# RS485.net
KiCad netlist of a schematic drawn in Altium Designer
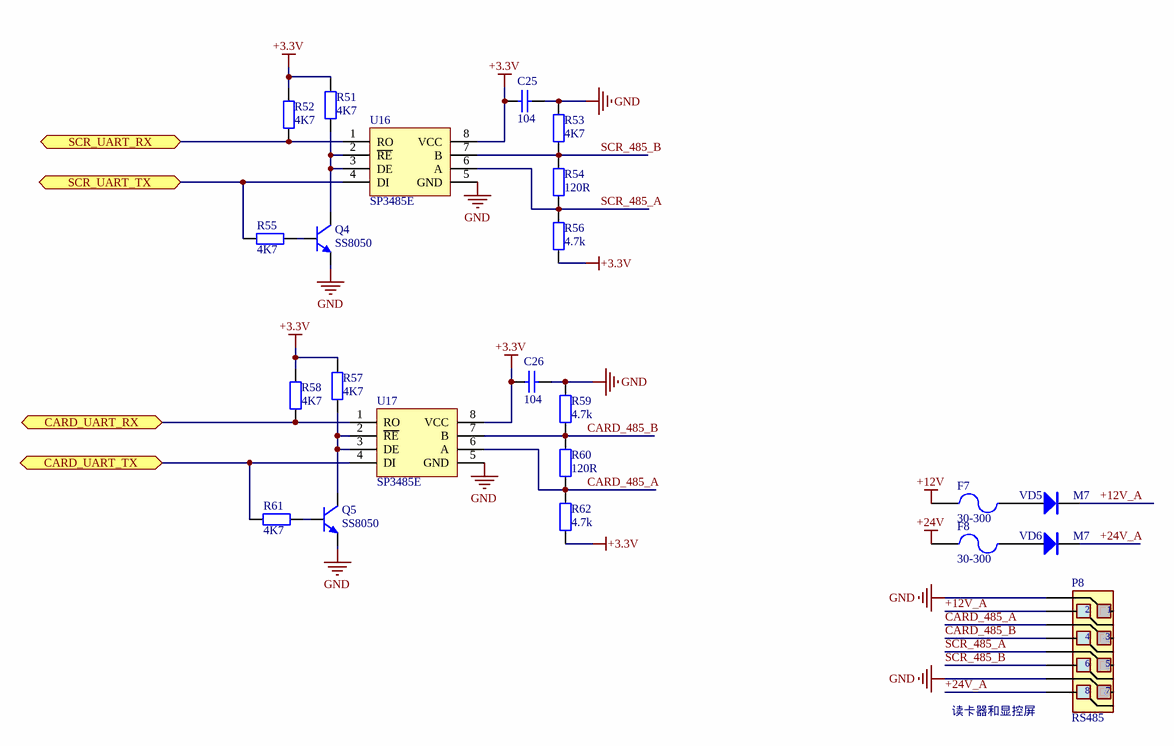
[diagram p0: RS485.SchDoc]

(export (version "E")
  (design (tool "Eeschema 10.0.6"))
  (components
    (comp (ref "C25")
      (value "104")
      (footprint "C 0805")
      (libsource (lib "YXF_ComponentLibrary") (part "Cap1"))
    )
    (comp (ref "C26")
      (value "104")
      (footprint "C 0805")
      (libsource (lib "YXF_ComponentLibrary") (part "Cap1"))
    )
    (comp (ref "F7")
      (value "30-300")
      (footprint "FU 1812")
      (description "Fuse")
      (fields (field (name "PUBLISHER") "Altium Limited"))
      (libsource (lib "YXF_ComponentLibrary") (part "Fuse 2"))
    )
    (comp (ref "F8")
      (value "30-300")
      (footprint "FU 1812")
      (description "Fuse")
      (fields (field (name "PUBLISHER") "Altium Limited"))
      (libsource (lib "YXF_ComponentLibrary") (part "Fuse 2"))
    )
    (comp (ref "P8")
      (value "RS485")
      (footprint "557-2x4")
      (description "接插件")
      (libsource (lib "YXF_ComponentLibrary") (part "557-2x4"))
    )
    (comp (ref "Q4")
      (value "SS8050")
      (footprint "SOT23-3N")
      (description "高频放大-NPN型")
      (fields (field (name "版权归属") "源创客"))
      (libsource (lib "三极管") (part "8050-SMD"))
    )
    (comp (ref "Q5")
      (value "SS8050")
      (footprint "SOT23-3N")
      (description "高频放大-NPN型")
      (fields (field (name "版权归属") "源创客"))
      (libsource (lib "三极管") (part "8050-SMD"))
    )
    (comp (ref "R51") (value "4K7") (footprint "R 0805") (libsource (lib "any") (part "Res1")))
    (comp (ref "R52") (value "4K7") (footprint "R 0805") (libsource (lib "any") (part "Res1")))
    (comp (ref "R53") (value "4K7") (footprint "R 0805") (libsource (lib "any") (part "Res1")))
    (comp (ref "R54") (value "120R") (footprint "R 0805") (libsource (lib "any") (part "Res1")))
    (comp (ref "R55") (value "4K7") (footprint "R 0805") (libsource (lib "") (part "Res1_1")))
    (comp (ref "R56") (value "4.7k") (footprint "R 0805") (libsource (lib "any") (part "Res1")))
    (comp (ref "R57") (value "4K7") (footprint "R 0805") (libsource (lib "any") (part "Res1")))
    (comp (ref "R58") (value "4K7") (footprint "R 0805") (libsource (lib "any") (part "Res1")))
    (comp (ref "R59") (value "4.7k") (footprint "R 0805") (libsource (lib "any") (part "Res1")))
    (comp (ref "R60") (value "120R") (footprint "R 0805") (libsource (lib "any") (part "Res1")))
    (comp (ref "R61") (value "4K7") (footprint "R 0805") (libsource (lib "") (part "Res1_1")))
    (comp (ref "R62") (value "4.7k") (footprint "R 0805") (libsource (lib "any") (part "Res1")))
    (comp (ref "U16") (value "SP3485E") (footprint "SOP8_N") (libsource (lib "YS_STM32f103") (part "SP3485")))
    (comp (ref "U17") (value "SP3485E") (footprint "SOP8_N") (libsource (lib "YS_STM32f103") (part "SP3485")))
    (comp (ref "VD5")
      (value "M7")
      (footprint "SMA")
      (description "整流二极管")
      (fields (field (name "版权归属") "源创客"))
      (libsource (lib "二极管-整流桥") (part "M7"))
    )
    (comp (ref "VD6")
      (value "M7")
      (footprint "SMA")
      (description "整流二极管")
      (fields (field (name "版权归属") "源创客"))
      (libsource (lib "二极管-整流桥") (part "M7"))
    )
  )
  (nets
    (net (code "1") (name "+3.3V") (class "Default")
      (node (ref "C25") (pin "2") (pinfunction "2_2") (pintype "passive"))
      (node (ref "C26") (pin "2") (pinfunction "2_2") (pintype "passive"))
      (node (ref "R51") (pin "2") (pinfunction "2_2") (pintype "passive"))
      (node (ref "R52") (pin "2") (pinfunction "2_2") (pintype "passive"))
      (node (ref "R56") (pin "1") (pinfunction "1_1") (pintype "passive"))
      (node (ref "R57") (pin "2") (pinfunction "2_2") (pintype "passive"))
      (node (ref "R58") (pin "2") (pinfunction "2_2") (pintype "passive"))
      (node (ref "R62") (pin "1") (pinfunction "1_1") (pintype "passive"))
      (node (ref "U16") (pin "8") (pinfunction "VCC_8") (pintype "passive"))
      (node (ref "U17") (pin "8") (pinfunction "VCC_8") (pintype "passive"))
    )
    (net (code "2") (name "+12V") (class "Default")
      (node (ref "F7") (pin "1") (pinfunction "1_1") (pintype "passive"))
    )
    (net (code "3") (name "+24V") (class "Default")
      (node (ref "F8") (pin "1") (pinfunction "1_1") (pintype "passive"))
    )
    (net (code "4") (name "/+12V_A") (class "Default")
      (node (ref "P8") (pin "2") (pinfunction "2_2") (pintype "passive"))
      (node (ref "VD5") (pin "2") (pinfunction "K_2") (pintype "passive"))
    )
    (net (code "5") (name "/+24V_A") (class "Default")
      (node (ref "P8") (pin "8") (pinfunction "8_8") (pintype "passive"))
      (node (ref "VD6") (pin "2") (pinfunction "K_2") (pintype "passive"))
    )
    (net (code "6") (name "/CARD_485_A") (class "Default")
      (node (ref "P8") (pin "3") (pinfunction "3_3") (pintype "passive"))
      (node (ref "R60") (pin "1") (pinfunction "1_1") (pintype "passive"))
      (node (ref "R62") (pin "2") (pinfunction "2_2") (pintype "passive"))
      (node (ref "U17") (pin "6") (pinfunction "A_6") (pintype "passive"))
    )
    (net (code "7") (name "/CARD_485_B") (class "Default")
      (node (ref "P8") (pin "4") (pinfunction "4_4") (pintype "passive"))
      (node (ref "R59") (pin "1") (pinfunction "1_1") (pintype "passive"))
      (node (ref "R60") (pin "2") (pinfunction "2_2") (pintype "passive"))
      (node (ref "U17") (pin "7") (pinfunction "B_7") (pintype "passive"))
    )
    (net (code "8") (name "/CARD_UART_RX") (class "Default")
      (node (ref "R58") (pin "1") (pinfunction "1_1") (pintype "passive"))
      (node (ref "U17") (pin "1") (pinfunction "RO_1") (pintype "passive"))
    )
    (net (code "9") (name "/CARD_UART_TX") (class "Default")
      (node (ref "R61") (pin "2") (pinfunction "2_2") (pintype "passive"))
      (node (ref "U17") (pin "4") (pinfunction "DI_4") (pintype "passive"))
    )
    (net (code "10") (name "/SCR_485_A") (class "Default")
      (node (ref "P8") (pin "5") (pinfunction "5_5") (pintype "passive"))
      (node (ref "R54") (pin "1") (pinfunction "1_1") (pintype "passive"))
      (node (ref "R56") (pin "2") (pinfunction "2_2") (pintype "passive"))
      (node (ref "U16") (pin "6") (pinfunction "A_6") (pintype "passive"))
    )
    (net (code "11") (name "/SCR_485_B") (class "Default")
      (node (ref "P8") (pin "6") (pinfunction "6_6") (pintype "passive"))
      (node (ref "R53") (pin "1") (pinfunction "1_1") (pintype "passive"))
      (node (ref "R54") (pin "2") (pinfunction "2_2") (pintype "passive"))
      (node (ref "U16") (pin "7") (pinfunction "B_7") (pintype "passive"))
    )
    (net (code "12") (name "/SCR_UART_RX") (class "Default")
      (node (ref "R52") (pin "1") (pinfunction "1_1") (pintype "passive"))
      (node (ref "U16") (pin "1") (pinfunction "RO_1") (pintype "passive"))
    )
    (net (code "13") (name "/SCR_UART_TX") (class "Default")
      (node (ref "R55") (pin "2") (pinfunction "2_2") (pintype "passive"))
      (node (ref "U16") (pin "4") (pinfunction "DI_4") (pintype "passive"))
    )
    (net (code "14") (name "GND") (class "Default")
      (node (ref "C25") (pin "1") (pinfunction "1_1") (pintype "passive"))
      (node (ref "C26") (pin "1") (pinfunction "1_1") (pintype "passive"))
      (node (ref "P8") (pin "1") (pinfunction "1_1") (pintype "passive"))
      (node (ref "P8") (pin "7") (pinfunction "7_7") (pintype "passive"))
      (node (ref "Q4") (pin "2") (pinfunction "E_2") (pintype "passive"))
      (node (ref "Q5") (pin "2") (pinfunction "E_2") (pintype "passive"))
      (node (ref "R53") (pin "2") (pinfunction "2_2") (pintype "passive"))
      (node (ref "R59") (pin "2") (pinfunction "2_2") (pintype "passive"))
      (node (ref "U16") (pin "5") (pinfunction "GND_5") (pintype "passive"))
      (node (ref "U17") (pin "5") (pinfunction "GND_5") (pintype "passive"))
    )
    (net (code "15") (name "Net-(Q4-B)") (class "Default")
      (node (ref "Q4") (pin "1") (pinfunction "B_1") (pintype "passive"))
      (node (ref "R55") (pin "1") (pinfunction "1_1") (pintype "passive"))
    )
    (net (code "16") (name "Net-(Q4-C)") (class "Default")
      (node (ref "Q4") (pin "3") (pinfunction "C_3") (pintype "passive"))
      (node (ref "R51") (pin "1") (pinfunction "1_1") (pintype "passive"))
      (node (ref "U16") (pin "2") (pinfunction "~{RE}_2") (pintype "passive"))
      (node (ref "U16") (pin "3") (pinfunction "DE_3") (pintype "passive"))
    )
    (net (code "17") (name "Net-(Q5-B)") (class "Default")
      (node (ref "Q5") (pin "1") (pinfunction "B_1") (pintype "passive"))
      (node (ref "R61") (pin "1") (pinfunction "1_1") (pintype "passive"))
    )
    (net (code "18") (name "Net-(Q5-C)") (class "Default")
      (node (ref "Q5") (pin "3") (pinfunction "C_3") (pintype "passive"))
      (node (ref "R57") (pin "1") (pinfunction "1_1") (pintype "passive"))
      (node (ref "U17") (pin "2") (pinfunction "~{RE}_2") (pintype "passive"))
      (node (ref "U17") (pin "3") (pinfunction "DE_3") (pintype "passive"))
    )
    (net (code "19") (name "Net-(VD5-A)") (class "Default")
      (node (ref "F7") (pin "2") (pinfunction "2_2") (pintype "passive"))
      (node (ref "VD5") (pin "1") (pinfunction "A_1") (pintype "passive"))
    )
    (net (code "20") (name "Net-(VD6-A)") (class "Default")
      (node (ref "F8") (pin "2") (pinfunction "2_2") (pintype "passive"))
      (node (ref "VD6") (pin "1") (pinfunction "A_1") (pintype "passive"))
    )
  )
)
